# Rotary_Switch_Potentiometer.net
KiCad netlist of a schematic drawn in EAGLE
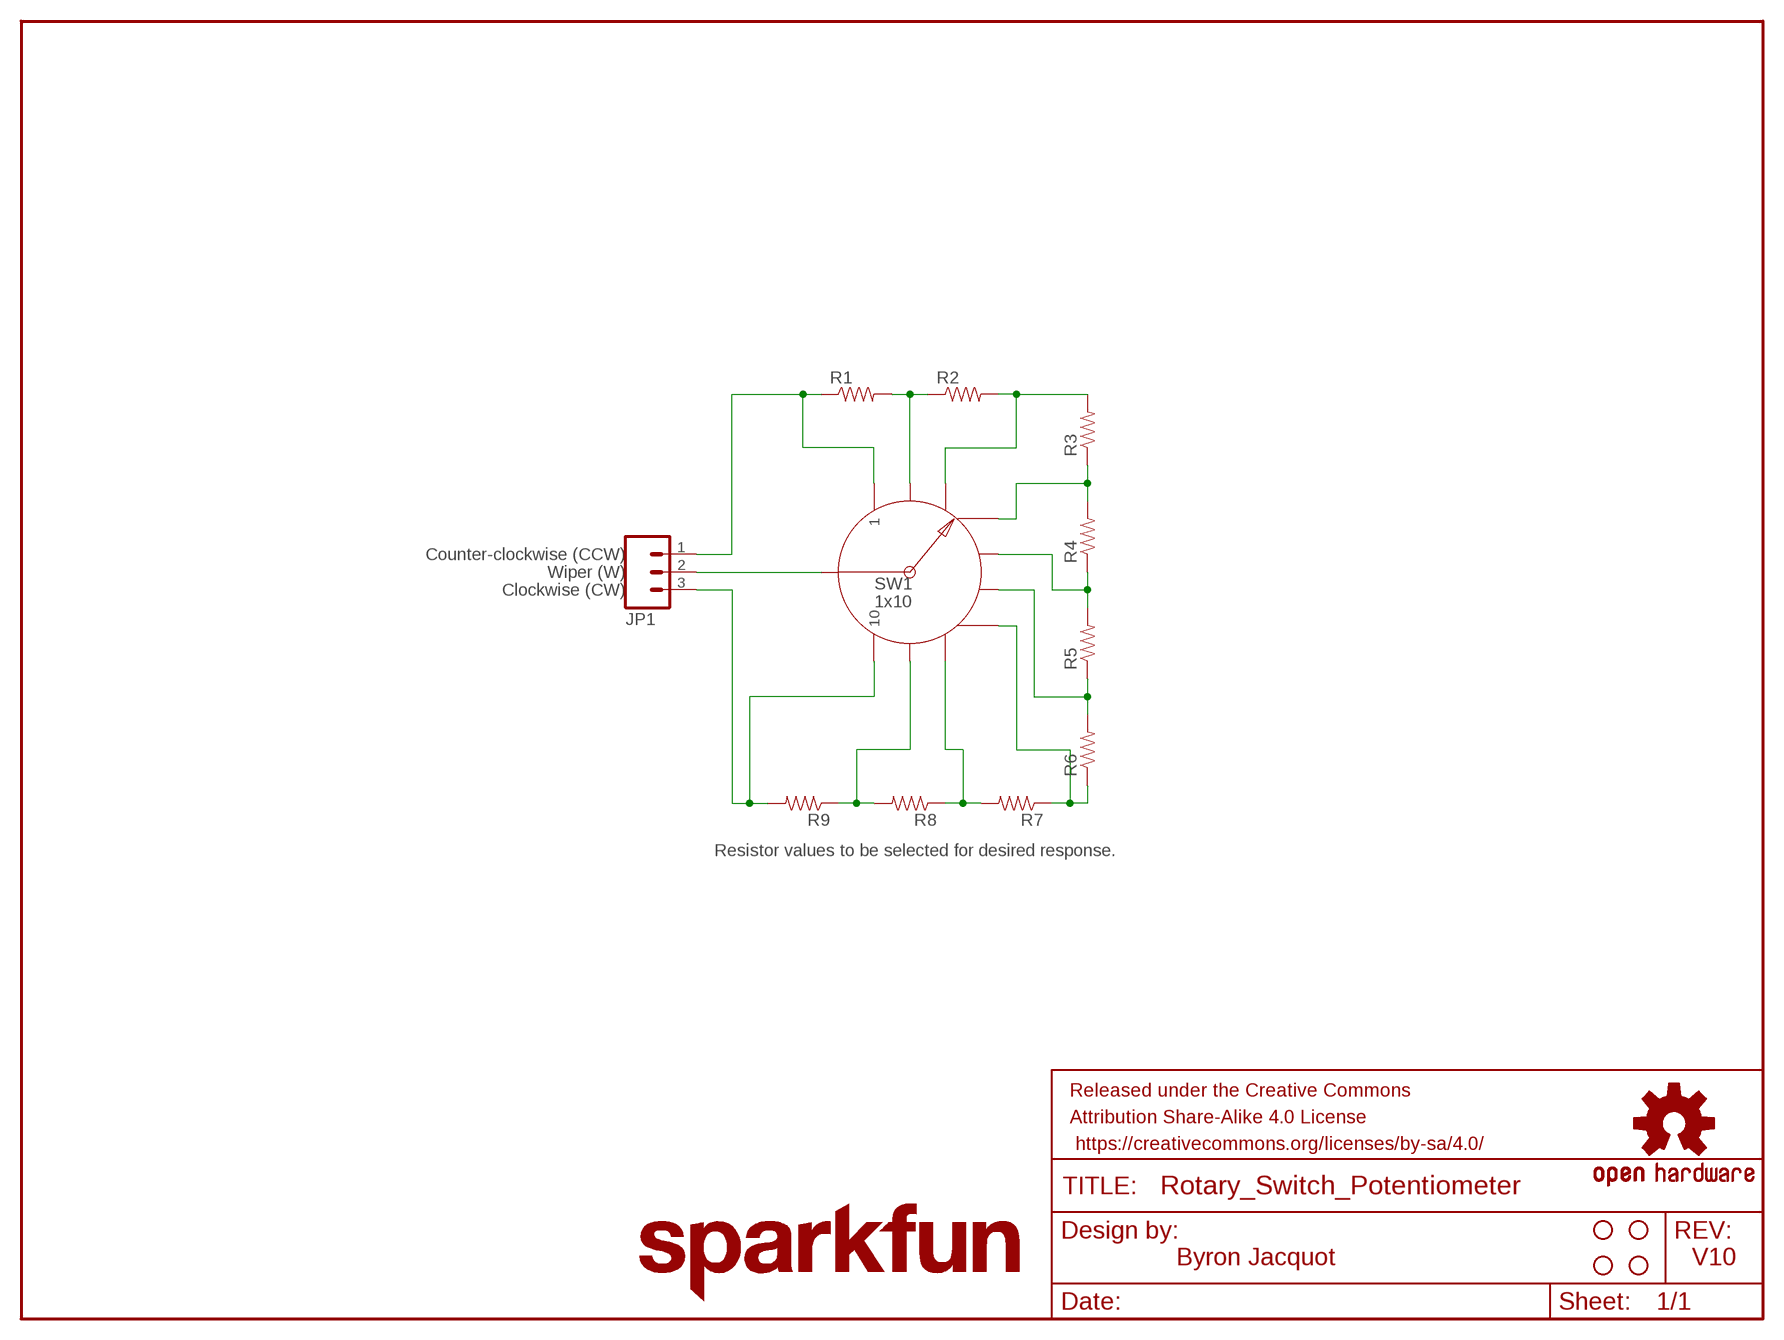
[diagram p0: schematic, sheet 1]

(export (version "E")
  (design (tool "Eeschema 10.0.6"))
  (components
    (comp (ref "FRAME1")
      (value "FRAME-LETTER")
      (footprint "eagle-import:CREATIVE_COMMONS")
      (libsource (lib "eagle-import") (part "FRAME-LETTER"))
    )
    (comp (ref "JP1")
      (value "M031X03_NO_SILK")
      (footprint "eagle-import:1X03_NO_SILK")
      (libsource (lib "eagle-import") (part "M031X03_NO_SILK"))
    )
    (comp (ref "LOGO1")
      (value "OSHW-LOGOM")
      (footprint "eagle-import:OSHW-LOGO-M")
      (libsource (lib "eagle-import") (part "OSHW-LOGOM"))
    )
    (comp (ref "LOGO3")
      (value "SFE_LOGO_NAME.1_INCH")
      (footprint "eagle-import:SFE_LOGO_NAME_.1")
      (libsource (lib "eagle-import") (part "SFE_LOGO_NAME.1_INCH"))
    )
    (comp (ref "R1")
      (value "RESISTORPTH-1/4W-VERT-KIT")
      (footprint "eagle-import:AXIAL-0.1EZ")
      (libsource (lib "eagle-import") (part "RESISTORPTH-1/4W-VERT-KIT"))
    )
    (comp (ref "R2")
      (value "RESISTORPTH-1/4W-VERT-KIT")
      (footprint "eagle-import:AXIAL-0.1EZ")
      (libsource (lib "eagle-import") (part "RESISTORPTH-1/4W-VERT-KIT"))
    )
    (comp (ref "R3")
      (value "RESISTORPTH-1/4W-VERT-KIT")
      (footprint "eagle-import:AXIAL-0.1EZ")
      (libsource (lib "eagle-import") (part "RESISTORPTH-1/4W-VERT-KIT"))
    )
    (comp (ref "R4")
      (value "RESISTORPTH-1/4W-VERT-KIT")
      (footprint "eagle-import:AXIAL-0.1EZ")
      (libsource (lib "eagle-import") (part "RESISTORPTH-1/4W-VERT-KIT"))
    )
    (comp (ref "R5")
      (value "RESISTORPTH-1/4W-VERT-KIT")
      (footprint "eagle-import:AXIAL-0.1EZ")
      (libsource (lib "eagle-import") (part "RESISTORPTH-1/4W-VERT-KIT"))
    )
    (comp (ref "R6")
      (value "RESISTORPTH-1/4W-VERT-KIT")
      (footprint "eagle-import:AXIAL-0.1EZ")
      (libsource (lib "eagle-import") (part "RESISTORPTH-1/4W-VERT-KIT"))
    )
    (comp (ref "R7")
      (value "RESISTORPTH-1/4W-VERT-KIT")
      (footprint "eagle-import:AXIAL-0.1EZ")
      (libsource (lib "eagle-import") (part "RESISTORPTH-1/4W-VERT-KIT"))
    )
    (comp (ref "R8")
      (value "RESISTORPTH-1/4W-VERT-KIT")
      (footprint "eagle-import:AXIAL-0.1EZ")
      (libsource (lib "eagle-import") (part "RESISTORPTH-1/4W-VERT-KIT"))
    )
    (comp (ref "R9")
      (value "RESISTORPTH-1/4W-VERT-KIT")
      (footprint "eagle-import:AXIAL-0.1EZ")
      (libsource (lib "eagle-import") (part "RESISTORPTH-1/4W-VERT-KIT"))
    )
    (comp (ref "STANDOFF1")
      (value "STAND-OFF")
      (footprint "eagle-import:STAND-OFF")
      (libsource (lib "eagle-import") (part "STAND-OFF"))
    )
    (comp (ref "STANDOFF2")
      (value "STAND-OFF")
      (footprint "eagle-import:STAND-OFF")
      (libsource (lib "eagle-import") (part "STAND-OFF"))
    )
    (comp (ref "STANDOFF5")
      (value "STAND-OFF")
      (footprint "eagle-import:STAND-OFF")
      (libsource (lib "eagle-import") (part "STAND-OFF"))
    )
    (comp (ref "STANDOFF6")
      (value "STAND-OFF")
      (footprint "eagle-import:STAND-OFF")
      (libsource (lib "eagle-import") (part "STAND-OFF"))
    )
    (comp (ref "SW1")
      (value "1x10")
      (footprint "eagle-import:ROTARY_SWITCH_1X10_KIT")
      (libsource (lib "eagle-import") (part "SWITCH_ROTARY_1X10KIT"))
    )
  )
  (nets
    (net (code "1") (name "Net-(JP1-Pad2)") (class "Default")
      (node (ref "JP1") (pin "2") (pinfunction "2_2") (pintype "passive"))
      (node (ref "SW1") (pin "COMMON") (pinfunction "COMMON_COMMON") (pintype "bidirectional"))
    )
    (net (code "2") (name "Net-(R1-1)") (class "Default")
      (node (ref "JP1") (pin "1") (pinfunction "1_1") (pintype "passive"))
      (node (ref "R1") (pin "P$1") (pinfunction "1_P$1") (pintype "passive"))
      (node (ref "SW1") (pin "1") (pinfunction "1_1") (pintype "bidirectional"))
    )
    (net (code "3") (name "Net-(R1-2)") (class "Default")
      (node (ref "R1") (pin "P$2") (pinfunction "2_P$2") (pintype "passive"))
      (node (ref "R2") (pin "P$1") (pinfunction "1_P$1") (pintype "passive"))
      (node (ref "SW1") (pin "2") (pinfunction "2_2") (pintype "bidirectional"))
    )
    (net (code "4") (name "Net-(R2-2)") (class "Default")
      (node (ref "R2") (pin "P$2") (pinfunction "2_P$2") (pintype "passive"))
      (node (ref "R3") (pin "P$2") (pinfunction "2_P$2") (pintype "passive"))
      (node (ref "SW1") (pin "3") (pinfunction "3_3") (pintype "bidirectional"))
    )
    (net (code "5") (name "Net-(R3-1)") (class "Default")
      (node (ref "R3") (pin "P$1") (pinfunction "1_P$1") (pintype "passive"))
      (node (ref "R4") (pin "P$2") (pinfunction "2_P$2") (pintype "passive"))
      (node (ref "SW1") (pin "4") (pinfunction "4_4") (pintype "bidirectional"))
    )
    (net (code "6") (name "Net-(R4-1)") (class "Default")
      (node (ref "R4") (pin "P$1") (pinfunction "1_P$1") (pintype "passive"))
      (node (ref "R5") (pin "P$2") (pinfunction "2_P$2") (pintype "passive"))
      (node (ref "SW1") (pin "5") (pinfunction "5_5") (pintype "bidirectional"))
    )
    (net (code "7") (name "Net-(R5-1)") (class "Default")
      (node (ref "R5") (pin "P$1") (pinfunction "1_P$1") (pintype "passive"))
      (node (ref "R6") (pin "P$2") (pinfunction "2_P$2") (pintype "passive"))
      (node (ref "SW1") (pin "6") (pinfunction "6_6") (pintype "bidirectional"))
    )
    (net (code "8") (name "Net-(R6-1)") (class "Default")
      (node (ref "R6") (pin "P$1") (pinfunction "1_P$1") (pintype "passive"))
      (node (ref "R7") (pin "P$1") (pinfunction "1_P$1") (pintype "passive"))
      (node (ref "SW1") (pin "7") (pinfunction "7_7") (pintype "bidirectional"))
    )
    (net (code "9") (name "Net-(R7-2)") (class "Default")
      (node (ref "R7") (pin "P$2") (pinfunction "2_P$2") (pintype "passive"))
      (node (ref "R8") (pin "P$1") (pinfunction "1_P$1") (pintype "passive"))
      (node (ref "SW1") (pin "8") (pinfunction "8_8") (pintype "bidirectional"))
    )
    (net (code "10") (name "Net-(R8-2)") (class "Default")
      (node (ref "R8") (pin "P$2") (pinfunction "2_P$2") (pintype "passive"))
      (node (ref "R9") (pin "P$1") (pinfunction "1_P$1") (pintype "passive"))
      (node (ref "SW1") (pin "9") (pinfunction "9_9") (pintype "bidirectional"))
    )
    (net (code "11") (name "Net-(R9-2)") (class "Default")
      (node (ref "JP1") (pin "3") (pinfunction "3_3") (pintype "passive"))
      (node (ref "R9") (pin "P$2") (pinfunction "2_P$2") (pintype "passive"))
      (node (ref "SW1") (pin "10") (pinfunction "10_10") (pintype "bidirectional"))
    )
  )
)
